# LVDS_IFC_DDS.net
KiCad netlist of a schematic drawn in Altium Designer
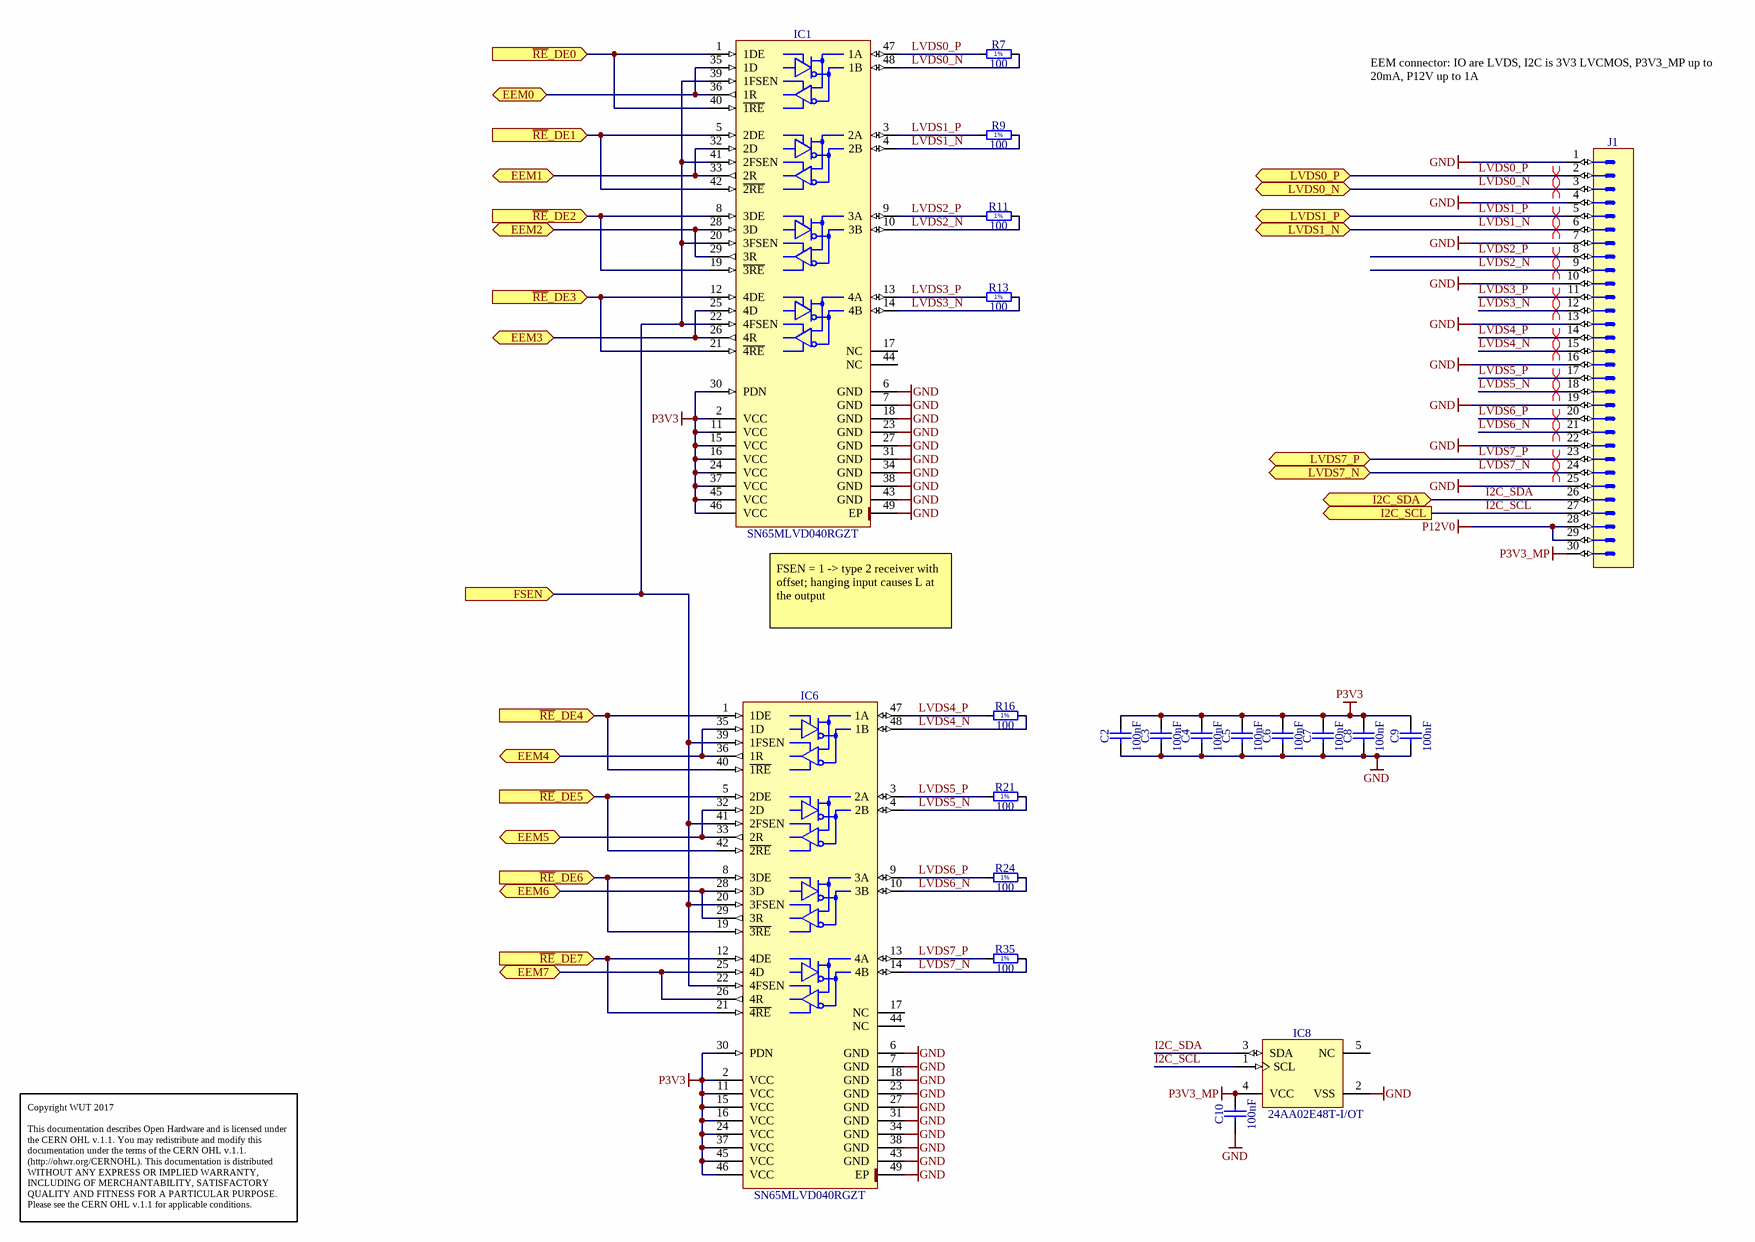
[diagram p0: LVDS_IFC_DDS.SchDoc]

(export (version "E")
  (design (tool "Eeschema 10.0.6"))
  (components
    (comp (ref "C2")
      (value "100nF")
      (footprint "CAPC1005X55N")
      (description "Non-polarised capacitor")
      (fields
        (field (name "PART NUMBER") "CC0402_100NF_16V_10%_X5R")
        (field (name "VOLTAGE") "16V")
        (field (name "AUTHOR") "CERN DEM JLC")
      )
      (libsource (lib "Capacitors") (part "Capacitor - non polarized"))
    )
    (comp (ref "C3")
      (value "100nF")
      (footprint "CAPC1005X55N")
      (description "Non-polarised capacitor")
      (fields
        (field (name "PART NUMBER") "CC0402_100NF_16V_10%_X5R")
        (field (name "VOLTAGE") "16V")
        (field (name "AUTHOR") "CERN DEM JLC")
      )
      (libsource (lib "Capacitors") (part "Capacitor - non polarized"))
    )
    (comp (ref "C4")
      (value "100nF")
      (footprint "CAPC1005X55N")
      (description "Non-polarised capacitor")
      (fields
        (field (name "PART NUMBER") "CC0402_100NF_16V_10%_X5R")
        (field (name "VOLTAGE") "16V")
        (field (name "AUTHOR") "CERN DEM JLC")
      )
      (libsource (lib "Capacitors") (part "Capacitor - non polarized"))
    )
    (comp (ref "C5")
      (value "100nF")
      (footprint "CAPC1005X55N")
      (description "Non-polarised capacitor")
      (fields
        (field (name "PART NUMBER") "CC0402_100NF_16V_10%_X5R")
        (field (name "VOLTAGE") "16V")
        (field (name "AUTHOR") "CERN DEM JLC")
      )
      (libsource (lib "Capacitors") (part "Capacitor - non polarized"))
    )
    (comp (ref "C6")
      (value "100nF")
      (footprint "CAPC1005X55N")
      (description "Non-polarised capacitor")
      (fields
        (field (name "PART NUMBER") "CC0402_100NF_16V_10%_X5R")
        (field (name "VOLTAGE") "16V")
        (field (name "AUTHOR") "CERN DEM JLC")
      )
      (libsource (lib "Capacitors") (part "Capacitor - non polarized"))
    )
    (comp (ref "C7")
      (value "100nF")
      (footprint "CAPC1005X55N")
      (description "Non-polarised capacitor")
      (fields
        (field (name "PART NUMBER") "CC0402_100NF_16V_10%_X5R")
        (field (name "VOLTAGE") "16V")
        (field (name "AUTHOR") "CERN DEM JLC")
      )
      (libsource (lib "Capacitors") (part "Capacitor - non polarized"))
    )
    (comp (ref "C8")
      (value "100nF")
      (footprint "CAPC1005X55N")
      (description "Non-polarised capacitor")
      (fields
        (field (name "PART NUMBER") "CC0402_100NF_16V_10%_X5R")
        (field (name "VOLTAGE") "16V")
        (field (name "AUTHOR") "CERN DEM JLC")
      )
      (libsource (lib "Capacitors") (part "Capacitor - non polarized"))
    )
    (comp (ref "C9")
      (value "100nF")
      (footprint "CAPC1005X55N")
      (description "Non-polarised capacitor")
      (fields
        (field (name "PART NUMBER") "CC0402_100NF_16V_10%_X5R")
        (field (name "VOLTAGE") "16V")
        (field (name "AUTHOR") "CERN DEM JLC")
      )
      (libsource (lib "Capacitors") (part "Capacitor - non polarized"))
    )
    (comp (ref "C10")
      (value "100nF")
      (footprint "CAPC1005X55N")
      (description "Non-polarised capacitor")
      (fields
        (field (name "PART NUMBER") "CC0402_100NF_16V_10%_X5R")
        (field (name "VOLTAGE") "16V")
        (field (name "AUTHOR") "CERN DEM JLC")
      )
      (libsource (lib "Capacitors") (part "Capacitor - non polarized"))
    )
    (comp (ref "IC1")
      (value "SN65MLVD040RGZT")
      (footprint "QFN50P700X700X100-49N-S420")
      (description "4-Channel Half-Duplex M-LVDS Line Transceiver")
      (fields (field (name "MANUFACTURER") "TEXAS INSTRUMENTS") (field (name "AUTHOR") "CERN DEM JLC"))
      (libsource (lib "ICs And Semiconductors") (part "SN65MLVD040"))
    )
    (comp (ref "IC6")
      (value "SN65MLVD040RGZT")
      (footprint "QFN50P700X700X100-49N-S420")
      (description "4-Channel Half-Duplex M-LVDS Line Transceiver")
      (fields (field (name "MANUFACTURER") "TEXAS INSTRUMENTS") (field (name "AUTHOR") "CERN DEM JLC"))
      (libsource (lib "ICs And Semiconductors") (part "SN65MLVD040"))
    )
    (comp (ref "IC8")
      (value "24AA02E48T-I/OT")
      (footprint "SOT95P280X145-5N")
      (description "1.7V-5.5V, 2K I2C Serial EEPROM With EUI-48 Node Identity")
      (fields (field (name "MANUFACTURER") "MICROCHIP TECHNOLOGY") (field (name "AUTHOR") "CERN DEM MR"))
      (libsource (lib "ICs And Semiconductors") (part "24AA02E48T-I/OT"))
    )
    (comp (ref "J1")
      (value "~")
      (footprint "3M_N2530-6002RB")
      (description "Connector 30 Male")
      (fields
        (field (name "PART NUMBER") "3M_N2530-6002RB")
        (field (name "MANUFACTURER") "3M")
        (field (name "AUTHOR") "CERN DEM JLC")
      )
      (libsource (lib "Connectors") (part "Connector 30 Male"))
    )
    (comp (ref "R7")
      (value "100")
      (footprint "RESC1005X40N")
      (description "Resistor - 1%")
      (fields
        (field (name "PART NUMBER") "R0402_100R_1%_0.1W_100PPM")
        (field (name "POWER") "0.1W")
        (field (name "AUTHOR") "CERN DEM JLC")
      )
      (libsource (lib "Resistors") (part "Resistor - 1%"))
    )
    (comp (ref "R9")
      (value "100")
      (footprint "RESC1005X40N")
      (description "Resistor - 1%")
      (fields
        (field (name "PART NUMBER") "R0402_100R_1%_0.1W_100PPM")
        (field (name "POWER") "0.1W")
        (field (name "AUTHOR") "CERN DEM JLC")
      )
      (libsource (lib "Resistors") (part "Resistor - 1%"))
    )
    (comp (ref "R11")
      (value "100")
      (footprint "RESC1005X40N")
      (description "Resistor - 1%")
      (fields
        (field (name "PART NUMBER") "R0402_100R_1%_0.1W_100PPM")
        (field (name "POWER") "0.1W")
        (field (name "AUTHOR") "CERN DEM JLC")
      )
      (libsource (lib "Resistors") (part "Resistor - 1%"))
    )
    (comp (ref "R13")
      (value "100")
      (footprint "RESC1005X40N")
      (description "Resistor - 1%")
      (fields
        (field (name "PART NUMBER") "R0402_100R_1%_0.1W_100PPM")
        (field (name "POWER") "0.1W")
        (field (name "AUTHOR") "CERN DEM JLC")
      )
      (libsource (lib "Resistors") (part "Resistor - 1%"))
    )
    (comp (ref "R16")
      (value "100")
      (footprint "RESC1005X40N")
      (description "Resistor - 1%")
      (fields
        (field (name "PART NUMBER") "R0402_100R_1%_0.1W_100PPM")
        (field (name "POWER") "0.1W")
        (field (name "AUTHOR") "CERN DEM JLC")
      )
      (libsource (lib "Resistors") (part "Resistor - 1%"))
    )
    (comp (ref "R21")
      (value "100")
      (footprint "RESC1005X40N")
      (description "Resistor - 1%")
      (fields
        (field (name "PART NUMBER") "R0402_100R_1%_0.1W_100PPM")
        (field (name "POWER") "0.1W")
        (field (name "AUTHOR") "CERN DEM JLC")
      )
      (libsource (lib "Resistors") (part "Resistor - 1%"))
    )
    (comp (ref "R24")
      (value "100")
      (footprint "RESC1005X40N")
      (description "Resistor - 1%")
      (fields
        (field (name "PART NUMBER") "R0402_100R_1%_0.1W_100PPM")
        (field (name "POWER") "0.1W")
        (field (name "AUTHOR") "CERN DEM JLC")
      )
      (libsource (lib "Resistors") (part "Resistor - 1%"))
    )
    (comp (ref "R35")
      (value "100")
      (footprint "RESC1005X40N")
      (description "Resistor - 1%")
      (fields
        (field (name "PART NUMBER") "R0402_100R_1%_0.1W_100PPM")
        (field (name "POWER") "0.1W")
        (field (name "AUTHOR") "CERN DEM JLC")
      )
      (libsource (lib "Resistors") (part "Resistor - 1%"))
    )
  )
  (nets
    (net (code "1") (name "/EEM0") (class "Default")
      (node (ref "IC1") (pin "35") (pinfunction "1D_35") (pintype "input"))
      (node (ref "IC1") (pin "36") (pinfunction "1R_36") (pintype "output"))
    )
    (net (code "2") (name "/EEM1") (class "Default")
      (node (ref "IC1") (pin "32") (pinfunction "2D_32") (pintype "input"))
      (node (ref "IC1") (pin "33") (pinfunction "2R_33") (pintype "output"))
    )
    (net (code "3") (name "/EEM2") (class "Default")
      (node (ref "IC1") (pin "28") (pinfunction "3D_28") (pintype "input"))
      (node (ref "IC1") (pin "29") (pinfunction "3R_29") (pintype "output"))
    )
    (net (code "4") (name "/EEM3") (class "Default")
      (node (ref "IC1") (pin "25") (pinfunction "4D_25") (pintype "input"))
      (node (ref "IC1") (pin "26") (pinfunction "4R_26") (pintype "output"))
    )
    (net (code "5") (name "/EEM4") (class "Default")
      (node (ref "IC6") (pin "35") (pinfunction "1D_35") (pintype "input"))
      (node (ref "IC6") (pin "36") (pinfunction "1R_36") (pintype "output"))
    )
    (net (code "6") (name "/EEM5") (class "Default")
      (node (ref "IC6") (pin "32") (pinfunction "2D_32") (pintype "input"))
      (node (ref "IC6") (pin "33") (pinfunction "2R_33") (pintype "output"))
    )
    (net (code "7") (name "/EEM6") (class "Default")
      (node (ref "IC6") (pin "28") (pinfunction "3D_28") (pintype "input"))
      (node (ref "IC6") (pin "29") (pinfunction "3R_29") (pintype "output"))
    )
    (net (code "8") (name "/EEM7") (class "Default")
      (node (ref "IC6") (pin "25") (pinfunction "4D_25") (pintype "input"))
      (node (ref "IC6") (pin "26") (pinfunction "4R_26") (pintype "output"))
    )
    (net (code "9") (name "/FSEN") (class "Default")
      (node (ref "IC1") (pin "20") (pinfunction "3FSEN_20") (pintype "input"))
      (node (ref "IC1") (pin "22") (pinfunction "4FSEN_22") (pintype "input"))
      (node (ref "IC1") (pin "39") (pinfunction "1FSEN_39") (pintype "input"))
      (node (ref "IC1") (pin "41") (pinfunction "2FSEN_41") (pintype "input"))
      (node (ref "IC6") (pin "20") (pinfunction "3FSEN_20") (pintype "input"))
      (node (ref "IC6") (pin "22") (pinfunction "4FSEN_22") (pintype "input"))
      (node (ref "IC6") (pin "39") (pinfunction "1FSEN_39") (pintype "input"))
      (node (ref "IC6") (pin "41") (pinfunction "2FSEN_41") (pintype "input"))
    )
    (net (code "10") (name "/I2C_SCL") (class "Default")
      (node (ref "IC8") (pin "1") (pinfunction "SCL_1") (pintype "input"))
      (node (ref "J1") (pin "27") (pinfunction "27_27") (pintype "bidirectional"))
    )
    (net (code "11") (name "/I2C_SDA") (class "Default")
      (node (ref "IC8") (pin "3") (pinfunction "SDA_3") (pintype "bidirectional"))
      (node (ref "J1") (pin "26") (pinfunction "26_26") (pintype "bidirectional"))
    )
    (net (code "12") (name "/LVDS0_N") (class "Default")
      (node (ref "IC1") (pin "48") (pinfunction "1B_48") (pintype "bidirectional"))
      (node (ref "J1") (pin "3") (pinfunction "3_3") (pintype "bidirectional"))
      (node (ref "R7") (pin "2") (pinfunction "2_2") (pintype "passive"))
    )
    (net (code "13") (name "/LVDS0_P") (class "Default")
      (node (ref "IC1") (pin "47") (pinfunction "1A_47") (pintype "bidirectional"))
      (node (ref "J1") (pin "2") (pinfunction "2_2") (pintype "bidirectional"))
      (node (ref "R7") (pin "1") (pinfunction "1_1") (pintype "passive"))
    )
    (net (code "14") (name "/LVDS1_N") (class "Default")
      (node (ref "IC1") (pin "4") (pinfunction "2B_4") (pintype "bidirectional"))
      (node (ref "J1") (pin "6") (pinfunction "6_6") (pintype "bidirectional"))
      (node (ref "R9") (pin "2") (pinfunction "2_2") (pintype "passive"))
    )
    (net (code "15") (name "/LVDS1_P") (class "Default")
      (node (ref "IC1") (pin "3") (pinfunction "2A_3") (pintype "bidirectional"))
      (node (ref "J1") (pin "5") (pinfunction "5_5") (pintype "bidirectional"))
      (node (ref "R9") (pin "1") (pinfunction "1_1") (pintype "passive"))
    )
    (net (code "16") (name "/LVDS2_N") (class "Default")
      (node (ref "IC1") (pin "10") (pinfunction "3B_10") (pintype "bidirectional"))
      (node (ref "J1") (pin "9") (pinfunction "9_9") (pintype "bidirectional"))
      (node (ref "R11") (pin "2") (pinfunction "2_2") (pintype "passive"))
    )
    (net (code "17") (name "/LVDS2_P") (class "Default")
      (node (ref "IC1") (pin "9") (pinfunction "3A_9") (pintype "bidirectional"))
      (node (ref "J1") (pin "8") (pinfunction "8_8") (pintype "bidirectional"))
      (node (ref "R11") (pin "1") (pinfunction "1_1") (pintype "passive"))
    )
    (net (code "18") (name "/LVDS3_N") (class "Default")
      (node (ref "IC1") (pin "14") (pinfunction "4B_14") (pintype "bidirectional"))
      (node (ref "J1") (pin "12") (pinfunction "12_12") (pintype "bidirectional"))
      (node (ref "R13") (pin "2") (pinfunction "2_2") (pintype "passive"))
    )
    (net (code "19") (name "/LVDS3_P") (class "Default")
      (node (ref "IC1") (pin "13") (pinfunction "4A_13") (pintype "bidirectional"))
      (node (ref "J1") (pin "11") (pinfunction "11_11") (pintype "bidirectional"))
      (node (ref "R13") (pin "1") (pinfunction "1_1") (pintype "passive"))
    )
    (net (code "20") (name "/LVDS4_N") (class "Default")
      (node (ref "IC6") (pin "48") (pinfunction "1B_48") (pintype "bidirectional"))
      (node (ref "J1") (pin "15") (pinfunction "15_15") (pintype "bidirectional"))
      (node (ref "R16") (pin "2") (pinfunction "2_2") (pintype "passive"))
    )
    (net (code "21") (name "/LVDS4_P") (class "Default")
      (node (ref "IC6") (pin "47") (pinfunction "1A_47") (pintype "bidirectional"))
      (node (ref "J1") (pin "14") (pinfunction "14_14") (pintype "bidirectional"))
      (node (ref "R16") (pin "1") (pinfunction "1_1") (pintype "passive"))
    )
    (net (code "22") (name "/LVDS5_N") (class "Default")
      (node (ref "IC6") (pin "4") (pinfunction "2B_4") (pintype "bidirectional"))
      (node (ref "J1") (pin "18") (pinfunction "18_18") (pintype "bidirectional"))
      (node (ref "R21") (pin "2") (pinfunction "2_2") (pintype "passive"))
    )
    (net (code "23") (name "/LVDS5_P") (class "Default")
      (node (ref "IC6") (pin "3") (pinfunction "2A_3") (pintype "bidirectional"))
      (node (ref "J1") (pin "17") (pinfunction "17_17") (pintype "bidirectional"))
      (node (ref "R21") (pin "1") (pinfunction "1_1") (pintype "passive"))
    )
    (net (code "24") (name "/LVDS6_N") (class "Default")
      (node (ref "IC6") (pin "10") (pinfunction "3B_10") (pintype "bidirectional"))
      (node (ref "J1") (pin "21") (pinfunction "21_21") (pintype "bidirectional"))
      (node (ref "R24") (pin "2") (pinfunction "2_2") (pintype "passive"))
    )
    (net (code "25") (name "/LVDS6_P") (class "Default")
      (node (ref "IC6") (pin "9") (pinfunction "3A_9") (pintype "bidirectional"))
      (node (ref "J1") (pin "20") (pinfunction "20_20") (pintype "bidirectional"))
      (node (ref "R24") (pin "1") (pinfunction "1_1") (pintype "passive"))
    )
    (net (code "26") (name "/LVDS7_N") (class "Default")
      (node (ref "IC6") (pin "14") (pinfunction "4B_14") (pintype "bidirectional"))
      (node (ref "J1") (pin "24") (pinfunction "24_24") (pintype "bidirectional"))
      (node (ref "R35") (pin "2") (pinfunction "2_2") (pintype "passive"))
    )
    (net (code "27") (name "/LVDS7_P") (class "Default")
      (node (ref "IC6") (pin "13") (pinfunction "4A_13") (pintype "bidirectional"))
      (node (ref "J1") (pin "23") (pinfunction "23_23") (pintype "bidirectional"))
      (node (ref "R35") (pin "1") (pinfunction "1_1") (pintype "passive"))
    )
    (net (code "28") (name "/~{RE}_DE0") (class "Default")
      (node (ref "IC1") (pin "1") (pinfunction "1DE_1") (pintype "input"))
      (node (ref "IC1") (pin "40") (pinfunction "~{1RE}_40") (pintype "input"))
    )
    (net (code "29") (name "/~{RE}_DE1") (class "Default")
      (node (ref "IC1") (pin "42") (pinfunction "~{2RE}_42") (pintype "input"))
      (node (ref "IC1") (pin "5") (pinfunction "2DE_5") (pintype "input"))
    )
    (net (code "30") (name "/~{RE}_DE2") (class "Default")
      (node (ref "IC1") (pin "19") (pinfunction "~{3RE}_19") (pintype "input"))
      (node (ref "IC1") (pin "8") (pinfunction "3DE_8") (pintype "input"))
    )
    (net (code "31") (name "/~{RE}_DE3") (class "Default")
      (node (ref "IC1") (pin "12") (pinfunction "4DE_12") (pintype "input"))
      (node (ref "IC1") (pin "21") (pinfunction "~{4RE}_21") (pintype "input"))
    )
    (net (code "32") (name "/~{RE}_DE4") (class "Default")
      (node (ref "IC6") (pin "1") (pinfunction "1DE_1") (pintype "input"))
      (node (ref "IC6") (pin "40") (pinfunction "~{1RE}_40") (pintype "input"))
    )
    (net (code "33") (name "/~{RE}_DE5") (class "Default")
      (node (ref "IC6") (pin "42") (pinfunction "~{2RE}_42") (pintype "input"))
      (node (ref "IC6") (pin "5") (pinfunction "2DE_5") (pintype "input"))
    )
    (net (code "34") (name "/~{RE}_DE6") (class "Default")
      (node (ref "IC6") (pin "19") (pinfunction "~{3RE}_19") (pintype "input"))
      (node (ref "IC6") (pin "8") (pinfunction "3DE_8") (pintype "input"))
    )
    (net (code "35") (name "/~{RE}_DE7") (class "Default")
      (node (ref "IC6") (pin "12") (pinfunction "4DE_12") (pintype "input"))
      (node (ref "IC6") (pin "21") (pinfunction "~{4RE}_21") (pintype "input"))
    )
    (net (code "36") (name "GND") (class "Default")
      (node (ref "C10") (pin "1") (pinfunction "1_1") (pintype "passive"))
      (node (ref "C2") (pin "1") (pinfunction "1_1") (pintype "passive"))
      (node (ref "C3") (pin "1") (pinfunction "1_1") (pintype "passive"))
      (node (ref "C4") (pin "1") (pinfunction "1_1") (pintype "passive"))
      (node (ref "C5") (pin "1") (pinfunction "1_1") (pintype "passive"))
      (node (ref "C6") (pin "1") (pinfunction "1_1") (pintype "passive"))
      (node (ref "C7") (pin "1") (pinfunction "1_1") (pintype "passive"))
      (node (ref "C8") (pin "1") (pinfunction "1_1") (pintype "passive"))
      (node (ref "C9") (pin "1") (pinfunction "1_1") (pintype "passive"))
      (node (ref "IC1") (pin "18") (pinfunction "GND_18") (pintype "power_in"))
      (node (ref "IC1") (pin "23") (pinfunction "GND_23") (pintype "power_in"))
      (node (ref "IC1") (pin "27") (pinfunction "GND_27") (pintype "power_in"))
      (node (ref "IC1") (pin "31") (pinfunction "GND_31") (pintype "power_in"))
      (node (ref "IC1") (pin "34") (pinfunction "GND_34") (pintype "power_in"))
      (node (ref "IC1") (pin "38") (pinfunction "GND_38") (pintype "power_in"))
      (node (ref "IC1") (pin "43") (pinfunction "GND_43") (pintype "power_in"))
      (node (ref "IC1") (pin "49") (pinfunction "EP_49") (pintype "power_in"))
      (node (ref "IC1") (pin "6") (pinfunction "GND_6") (pintype "power_in"))
      (node (ref "IC1") (pin "7") (pinfunction "GND_7") (pintype "power_in"))
      (node (ref "IC6") (pin "18") (pinfunction "GND_18") (pintype "power_in"))
      (node (ref "IC6") (pin "23") (pinfunction "GND_23") (pintype "power_in"))
      (node (ref "IC6") (pin "27") (pinfunction "GND_27") (pintype "power_in"))
      (node (ref "IC6") (pin "31") (pinfunction "GND_31") (pintype "power_in"))
      (node (ref "IC6") (pin "34") (pinfunction "GND_34") (pintype "power_in"))
      (node (ref "IC6") (pin "38") (pinfunction "GND_38") (pintype "power_in"))
      (node (ref "IC6") (pin "43") (pinfunction "GND_43") (pintype "power_in"))
      (node (ref "IC6") (pin "49") (pinfunction "EP_49") (pintype "power_in"))
      (node (ref "IC6") (pin "6") (pinfunction "GND_6") (pintype "power_in"))
      (node (ref "IC6") (pin "7") (pinfunction "GND_7") (pintype "power_in"))
      (node (ref "IC8") (pin "2") (pinfunction "VSS_2") (pintype "power_in"))
      (node (ref "J1") (pin "1") (pinfunction "1_1") (pintype "bidirectional"))
      (node (ref "J1") (pin "10") (pinfunction "10_10") (pintype "bidirectional"))
      (node (ref "J1") (pin "13") (pinfunction "13_13") (pintype "bidirectional"))
      (node (ref "J1") (pin "16") (pinfunction "16_16") (pintype "bidirectional"))
      (node (ref "J1") (pin "19") (pinfunction "19_19") (pintype "bidirectional"))
      (node (ref "J1") (pin "22") (pinfunction "22_22") (pintype "bidirectional"))
      (node (ref "J1") (pin "25") (pinfunction "25_25") (pintype "bidirectional"))
      (node (ref "J1") (pin "4") (pinfunction "4_4") (pintype "bidirectional"))
      (node (ref "J1") (pin "7") (pinfunction "7_7") (pintype "bidirectional"))
    )
    (net (code "37") (name "P3V3") (class "Default")
      (node (ref "C2") (pin "2") (pinfunction "2_2") (pintype "passive"))
      (node (ref "C3") (pin "2") (pinfunction "2_2") (pintype "passive"))
      (node (ref "C4") (pin "2") (pinfunction "2_2") (pintype "passive"))
      (node (ref "C5") (pin "2") (pinfunction "2_2") (pintype "passive"))
      (node (ref "C6") (pin "2") (pinfunction "2_2") (pintype "passive"))
      (node (ref "C7") (pin "2") (pinfunction "2_2") (pintype "passive"))
      (node (ref "C8") (pin "2") (pinfunction "2_2") (pintype "passive"))
      (node (ref "C9") (pin "2") (pinfunction "2_2") (pintype "passive"))
      (node (ref "IC1") (pin "11") (pinfunction "VCC_11") (pintype "power_in"))
      (node (ref "IC1") (pin "15") (pinfunction "VCC_15") (pintype "power_in"))
      (node (ref "IC1") (pin "16") (pinfunction "VCC_16") (pintype "power_in"))
      (node (ref "IC1") (pin "2") (pinfunction "VCC_2") (pintype "power_in"))
      (node (ref "IC1") (pin "24") (pinfunction "VCC_24") (pintype "power_in"))
      (node (ref "IC1") (pin "30") (pinfunction "PDN_30") (pintype "input"))
      (node (ref "IC1") (pin "37") (pinfunction "VCC_37") (pintype "power_in"))
      (node (ref "IC1") (pin "45") (pinfunction "VCC_45") (pintype "power_in"))
      (node (ref "IC1") (pin "46") (pinfunction "VCC_46") (pintype "power_in"))
      (node (ref "IC6") (pin "11") (pinfunction "VCC_11") (pintype "power_in"))
      (node (ref "IC6") (pin "15") (pinfunction "VCC_15") (pintype "power_in"))
      (node (ref "IC6") (pin "16") (pinfunction "VCC_16") (pintype "power_in"))
      (node (ref "IC6") (pin "2") (pinfunction "VCC_2") (pintype "power_in"))
      (node (ref "IC6") (pin "24") (pinfunction "VCC_24") (pintype "power_in"))
      (node (ref "IC6") (pin "30") (pinfunction "PDN_30") (pintype "input"))
      (node (ref "IC6") (pin "37") (pinfunction "VCC_37") (pintype "power_in"))
      (node (ref "IC6") (pin "45") (pinfunction "VCC_45") (pintype "power_in"))
      (node (ref "IC6") (pin "46") (pinfunction "VCC_46") (pintype "power_in"))
    )
    (net (code "38") (name "P3V3_MP") (class "Default")
      (node (ref "C10") (pin "2") (pinfunction "2_2") (pintype "passive"))
      (node (ref "IC8") (pin "4") (pinfunction "VCC_4") (pintype "power_in"))
      (node (ref "J1") (pin "30") (pinfunction "30_30") (pintype "bidirectional"))
    )
    (net (code "39") (name "P12V0") (class "Default")
      (node (ref "J1") (pin "28") (pinfunction "28_28") (pintype "bidirectional"))
      (node (ref "J1") (pin "29") (pinfunction "29_29") (pintype "bidirectional"))
    )
    (net (code "40") (name "unconnected-(IC1-NC-Pad17)") (class "Default")
      (node (ref "IC1") (pin "17") (pinfunction "NC_17") (pintype "passive"))
    )
    (net (code "41") (name "unconnected-(IC1-NC-Pad44)") (class "Default")
      (node (ref "IC1") (pin "44") (pinfunction "NC_44") (pintype "passive"))
    )
    (net (code "42") (name "unconnected-(IC6-NC-Pad17)") (class "Default")
      (node (ref "IC6") (pin "17") (pinfunction "NC_17") (pintype "passive"))
    )
    (net (code "43") (name "unconnected-(IC6-NC-Pad44)") (class "Default")
      (node (ref "IC6") (pin "44") (pinfunction "NC_44") (pintype "passive"))
    )
    (net (code "44") (name "unconnected-(IC8-NC-Pad5)") (class "Default")
      (node (ref "IC8") (pin "5") (pinfunction "NC_5") (pintype "passive"))
    )
  )
)
